# TSAL.net
KiCad netlist of a schematic drawn in EAGLE
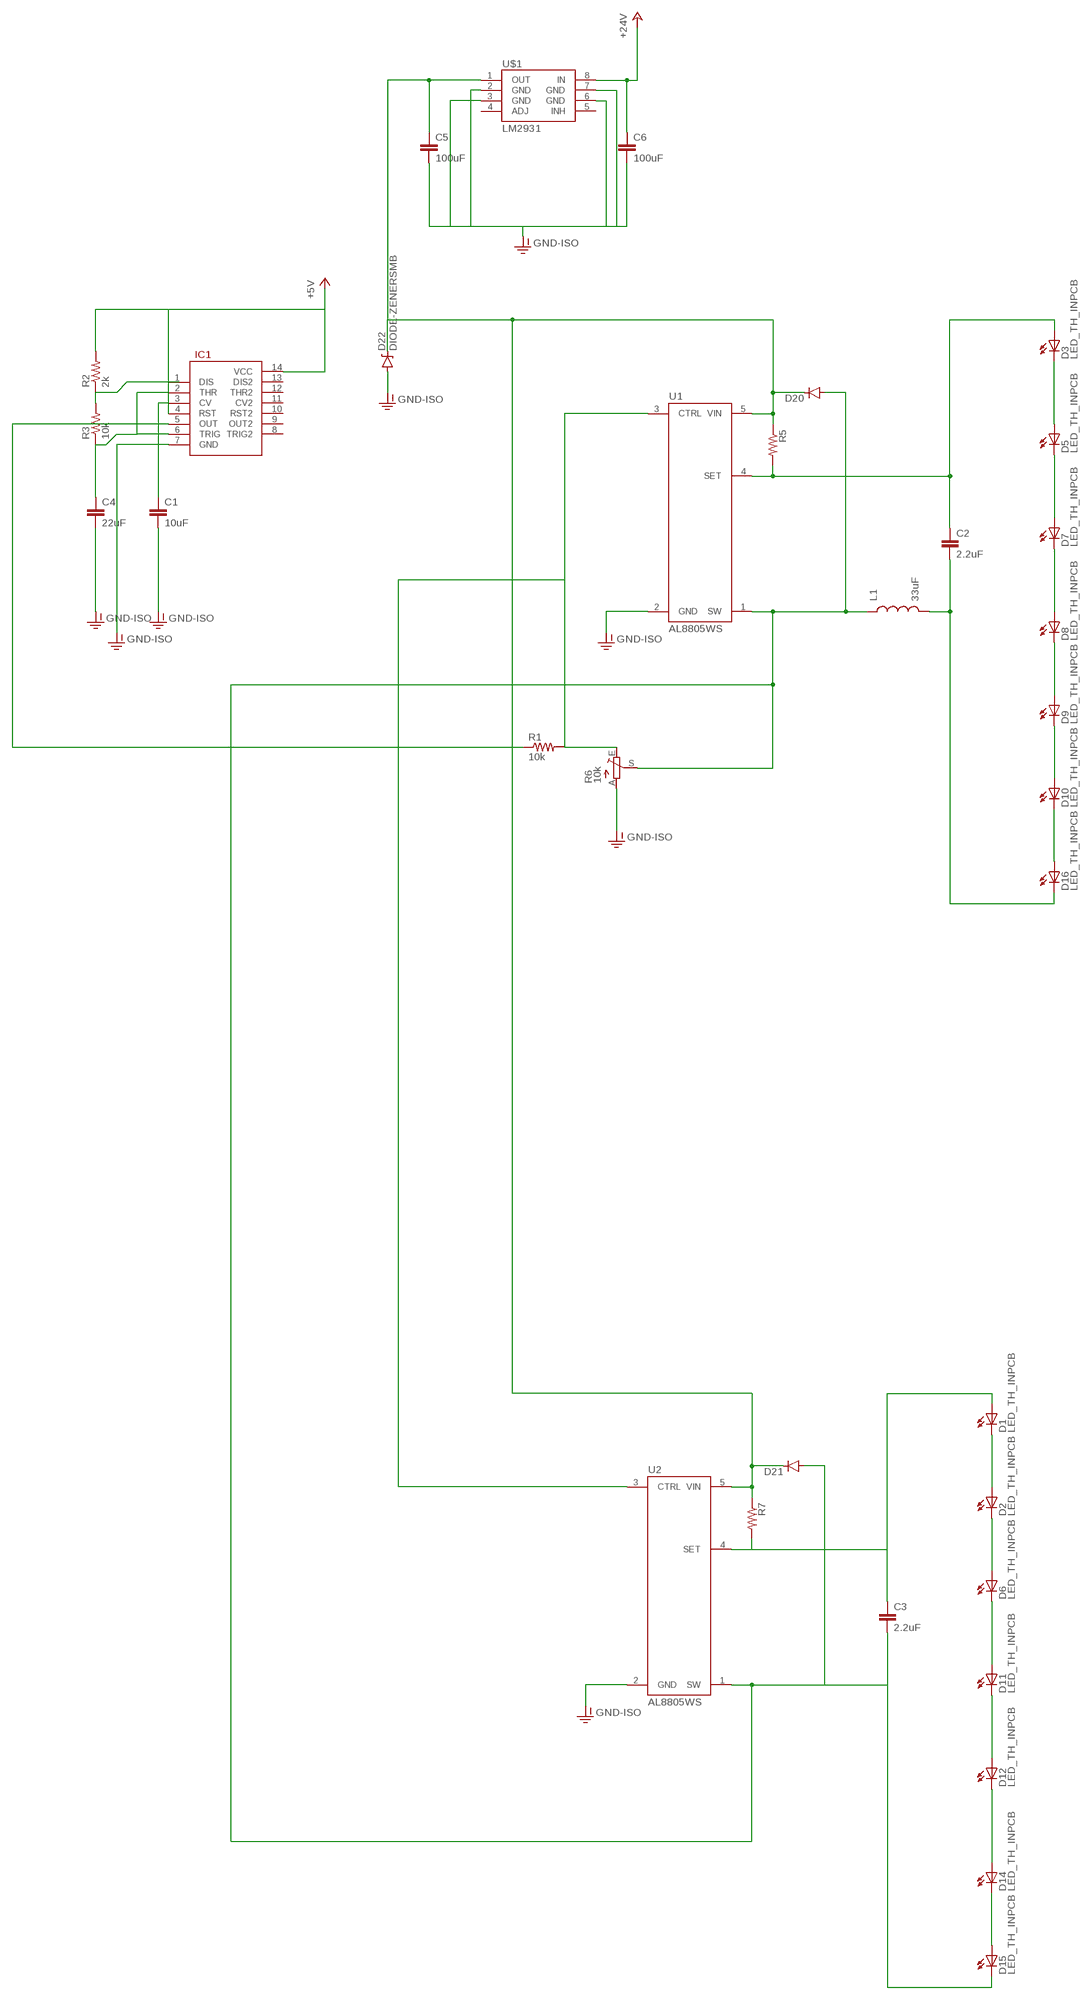
[diagram p0: schematic, sheet 1]

(export (version "E")
  (design (tool "Eeschema 10.0.6"))
  (components
    (comp (ref "C1")
      (value "10uF")
      (footprint "eagle-import:0805")
      (libsource (lib "eagle-import") (part "CAP0805"))
    )
    (comp (ref "C2")
      (value "2.2uF")
      (footprint "eagle-import:0805")
      (libsource (lib "eagle-import") (part "CAP0805"))
    )
    (comp (ref "C3")
      (value "2.2uF")
      (footprint "eagle-import:0805")
      (libsource (lib "eagle-import") (part "CAP0805"))
    )
    (comp (ref "C4")
      (value "22uF")
      (footprint "eagle-import:0805")
      (libsource (lib "eagle-import") (part "CAP0805"))
    )
    (comp (ref "C5")
      (value "100uF")
      (footprint "eagle-import:0805")
      (libsource (lib "eagle-import") (part "CAP0805"))
    )
    (comp (ref "C6")
      (value "100uF")
      (footprint "eagle-import:0805")
      (libsource (lib "eagle-import") (part "CAP0805"))
    )
    (comp (ref "D1")
      (value "LED_TH_INPCB")
      (footprint "eagle-import:5MM_TH_INDENT")
      (libsource (lib "eagle-import") (part "LED_TH_INPCB"))
    )
    (comp (ref "D2")
      (value "LED_TH_INPCB")
      (footprint "eagle-import:5MM_TH_INDENT")
      (libsource (lib "eagle-import") (part "LED_TH_INPCB"))
    )
    (comp (ref "D3")
      (value "LED_TH_INPCB")
      (footprint "eagle-import:5MM_TH_INDENT")
      (libsource (lib "eagle-import") (part "LED_TH_INPCB"))
    )
    (comp (ref "D5")
      (value "LED_TH_INPCB")
      (footprint "eagle-import:5MM_TH_INDENT")
      (libsource (lib "eagle-import") (part "LED_TH_INPCB"))
    )
    (comp (ref "D6")
      (value "LED_TH_INPCB")
      (footprint "eagle-import:5MM_TH_INDENT")
      (libsource (lib "eagle-import") (part "LED_TH_INPCB"))
    )
    (comp (ref "D7")
      (value "LED_TH_INPCB")
      (footprint "eagle-import:5MM_TH_INDENT")
      (libsource (lib "eagle-import") (part "LED_TH_INPCB"))
    )
    (comp (ref "D8")
      (value "LED_TH_INPCB")
      (footprint "eagle-import:5MM_TH_INDENT")
      (libsource (lib "eagle-import") (part "LED_TH_INPCB"))
    )
    (comp (ref "D9")
      (value "LED_TH_INPCB")
      (footprint "eagle-import:5MM_TH_INDENT")
      (libsource (lib "eagle-import") (part "LED_TH_INPCB"))
    )
    (comp (ref "D10")
      (value "LED_TH_INPCB")
      (footprint "eagle-import:5MM_TH_INDENT")
      (libsource (lib "eagle-import") (part "LED_TH_INPCB"))
    )
    (comp (ref "D11")
      (value "LED_TH_INPCB")
      (footprint "eagle-import:5MM_TH_INDENT")
      (libsource (lib "eagle-import") (part "LED_TH_INPCB"))
    )
    (comp (ref "D12")
      (value "LED_TH_INPCB")
      (footprint "eagle-import:5MM_TH_INDENT")
      (libsource (lib "eagle-import") (part "LED_TH_INPCB"))
    )
    (comp (ref "D14")
      (value "LED_TH_INPCB")
      (footprint "eagle-import:5MM_TH_INDENT")
      (libsource (lib "eagle-import") (part "LED_TH_INPCB"))
    )
    (comp (ref "D15")
      (value "LED_TH_INPCB")
      (footprint "eagle-import:5MM_TH_INDENT")
      (libsource (lib "eagle-import") (part "LED_TH_INPCB"))
    )
    (comp (ref "D16")
      (value "LED_TH_INPCB")
      (footprint "eagle-import:5MM_TH_INDENT")
      (libsource (lib "eagle-import") (part "LED_TH_INPCB"))
    )
    (comp (ref "D20")
      (value "DIODESMB")
      (footprint "eagle-import:SMB-DIODE")
      (libsource (lib "eagle-import") (part "DIODESMB"))
    )
    (comp (ref "D21")
      (value "DIODESMB")
      (footprint "eagle-import:SMB-DIODE")
      (libsource (lib "eagle-import") (part "DIODESMB"))
    )
    (comp (ref "D22")
      (value "DIODE-ZENERSMB")
      (footprint "eagle-import:SMB-DIODE")
      (libsource (lib "eagle-import") (part "DIODE-ZENERSMB"))
    )
    (comp (ref "IC1")
      (value "556")
      (footprint "eagle-import:DIL14")
      (libsource (lib "eagle-import") (part "556"))
    )
    (comp (ref "L1")
      (value "33uF")
      (footprint "eagle-import:0805")
      (libsource (lib "eagle-import") (part "INDUCTOR0805"))
    )
    (comp (ref "R1")
      (value "10k")
      (footprint "eagle-import:0805")
      (libsource (lib "eagle-import") (part "RESISTOR0805-RES"))
    )
    (comp (ref "R2")
      (value "2k")
      (footprint "eagle-import:0805")
      (libsource (lib "eagle-import") (part "RESISTOR0805-RES"))
    )
    (comp (ref "R3")
      (value "10k")
      (footprint "eagle-import:0805")
      (libsource (lib "eagle-import") (part "RESISTOR0805-RES"))
    )
    (comp (ref "R5")
      (value "RESISTOR0805-RES")
      (footprint "eagle-import:0805")
      (libsource (lib "eagle-import") (part "RESISTOR0805-RES"))
    )
    (comp (ref "R6")
      (value "10k")
      (footprint "eagle-import:B25P")
      (libsource (lib "eagle-import") (part "TRIM_EU-B25P"))
    )
    (comp (ref "R7")
      (value "RESISTOR0805-RES")
      (footprint "eagle-import:0805")
      (libsource (lib "eagle-import") (part "RESISTOR0805-RES"))
    )
    (comp (ref "U$1")
      (value "LM2931")
      (footprint "eagle-import:SO08")
      (libsource (lib "eagle-import") (part "LM2931"))
    )
    (comp (ref "U1")
      (value "AL8805WS")
      (footprint "eagle-import:SOT23-5")
      (libsource (lib "eagle-import") (part "AL8805"))
    )
    (comp (ref "U2")
      (value "AL8805WS")
      (footprint "eagle-import:SOT23-5")
      (libsource (lib "eagle-import") (part "AL8805"))
    )
  )
  (nets
    (net (code "1") (name "+5V") (class "Default")
      (node (ref "IC1") (pin "14") (pinfunction "VCC_14") (pintype "bidirectional"))
      (node (ref "IC1") (pin "4") (pinfunction "RST_4") (pintype "bidirectional"))
      (node (ref "R2") (pin "2") (pinfunction "2_2") (pintype "passive"))
    )
    (net (code "2") (name "+24V") (class "Default")
      (node (ref "C6") (pin "1") (pinfunction "1_1") (pintype "passive"))
      (node (ref "U$1") (pin "8") (pinfunction "IN_8") (pintype "bidirectional"))
    )
    (net (code "3") (name "GND-ISO") (class "Default")
      (node (ref "C1") (pin "2") (pinfunction "2_2") (pintype "passive"))
      (node (ref "C4") (pin "2") (pinfunction "2_2") (pintype "passive"))
      (node (ref "C5") (pin "2") (pinfunction "2_2") (pintype "passive"))
      (node (ref "C6") (pin "2") (pinfunction "2_2") (pintype "passive"))
      (node (ref "D22") (pin "A") (pinfunction "A_A") (pintype "passive"))
      (node (ref "IC1") (pin "7") (pinfunction "GND_7") (pintype "bidirectional"))
      (node (ref "R6") (pin "A") (pinfunction "A_A") (pintype "passive"))
      (node (ref "U$1") (pin "2") (pinfunction "GND_2") (pintype "bidirectional"))
      (node (ref "U$1") (pin "3") (pinfunction "GND_3") (pintype "bidirectional"))
      (node (ref "U$1") (pin "6") (pinfunction "GND_6") (pintype "bidirectional"))
      (node (ref "U$1") (pin "7") (pinfunction "GND_7") (pintype "bidirectional"))
      (node (ref "U1") (pin "2") (pinfunction "GND_2") (pintype "bidirectional"))
      (node (ref "U2") (pin "2") (pinfunction "GND_2") (pintype "bidirectional"))
    )
    (net (code "4") (name "Net-(C2-Pad2)") (class "Default")
      (node (ref "C2") (pin "2") (pinfunction "2_2") (pintype "passive"))
      (node (ref "D16") (pin "C") (pinfunction "C_C") (pintype "passive"))
      (node (ref "L1") (pin "2") (pinfunction "2_2") (pintype "passive"))
    )
    (net (code "5") (name "Net-(D1-PadC)") (class "Default")
      (node (ref "D1") (pin "C") (pinfunction "C_C") (pintype "passive"))
      (node (ref "D2") (pin "A") (pinfunction "A_A") (pintype "passive"))
    )
    (net (code "6") (name "Net-(D2-PadC)") (class "Default")
      (node (ref "D2") (pin "C") (pinfunction "C_C") (pintype "passive"))
      (node (ref "D6") (pin "A") (pinfunction "A_A") (pintype "passive"))
    )
    (net (code "7") (name "Net-(D3-PadC)") (class "Default")
      (node (ref "D3") (pin "C") (pinfunction "C_C") (pintype "passive"))
      (node (ref "D5") (pin "A") (pinfunction "A_A") (pintype "passive"))
    )
    (net (code "8") (name "Net-(D5-PadC)") (class "Default")
      (node (ref "D5") (pin "C") (pinfunction "C_C") (pintype "passive"))
      (node (ref "D7") (pin "A") (pinfunction "A_A") (pintype "passive"))
    )
    (net (code "9") (name "Net-(D7-PadC)") (class "Default")
      (node (ref "D7") (pin "C") (pinfunction "C_C") (pintype "passive"))
      (node (ref "D8") (pin "A") (pinfunction "A_A") (pintype "passive"))
    )
    (net (code "10") (name "Net-(D8-PadC)") (class "Default")
      (node (ref "D8") (pin "C") (pinfunction "C_C") (pintype "passive"))
      (node (ref "D9") (pin "A") (pinfunction "A_A") (pintype "passive"))
    )
    (net (code "11") (name "Net-(D10-PadA)") (class "Default")
      (node (ref "D10") (pin "A") (pinfunction "A_A") (pintype "passive"))
      (node (ref "D9") (pin "C") (pinfunction "C_C") (pintype "passive"))
    )
    (net (code "12") (name "Net-(D10-PadC)") (class "Default")
      (node (ref "D10") (pin "C") (pinfunction "C_C") (pintype "passive"))
      (node (ref "D16") (pin "A") (pinfunction "A_A") (pintype "passive"))
    )
    (net (code "13") (name "Net-(D11-PadA)") (class "Default")
      (node (ref "D11") (pin "A") (pinfunction "A_A") (pintype "passive"))
      (node (ref "D6") (pin "C") (pinfunction "C_C") (pintype "passive"))
    )
    (net (code "14") (name "Net-(D11-PadC)") (class "Default")
      (node (ref "D11") (pin "C") (pinfunction "C_C") (pintype "passive"))
      (node (ref "D12") (pin "A") (pinfunction "A_A") (pintype "passive"))
    )
    (net (code "15") (name "Net-(D12-PadC)") (class "Default")
      (node (ref "D12") (pin "C") (pinfunction "C_C") (pintype "passive"))
      (node (ref "D14") (pin "A") (pinfunction "A_A") (pintype "passive"))
    )
    (net (code "16") (name "Net-(D14-PadC)") (class "Default")
      (node (ref "D14") (pin "C") (pinfunction "C_C") (pintype "passive"))
      (node (ref "D15") (pin "A") (pinfunction "A_A") (pintype "passive"))
    )
    (net (code "17") (name "Net-(IC1-CV)") (class "Default")
      (node (ref "C1") (pin "1") (pinfunction "1_1") (pintype "passive"))
      (node (ref "IC1") (pin "3") (pinfunction "CV_3") (pintype "bidirectional"))
    )
    (net (code "18") (name "Net-(IC1-OUT)") (class "Default")
      (node (ref "IC1") (pin "5") (pinfunction "OUT_5") (pintype "bidirectional"))
      (node (ref "R1") (pin "1") (pinfunction "1_1") (pintype "passive"))
    )
    (net (code "19") (name "Net-(IC1-THR)") (class "Default")
      (node (ref "C4") (pin "1") (pinfunction "1_1") (pintype "passive"))
      (node (ref "IC1") (pin "2") (pinfunction "THR_2") (pintype "bidirectional"))
      (node (ref "IC1") (pin "6") (pinfunction "TRIG_6") (pintype "bidirectional"))
      (node (ref "R3") (pin "1") (pinfunction "1_1") (pintype "passive"))
    )
    (net (code "20") (name "Net-(R2-Pad1)") (class "Default")
      (node (ref "R2") (pin "1") (pinfunction "1_1") (pintype "passive"))
      (node (ref "R3") (pin "2") (pinfunction "2_2") (pintype "passive"))
    )
    (net (code "21") (name "Net-(U$1-OUT)") (class "Default")
      (node (ref "C5") (pin "1") (pinfunction "1_1") (pintype "passive"))
      (node (ref "D20") (pin "C") (pinfunction "C_C") (pintype "passive"))
      (node (ref "D21") (pin "C") (pinfunction "C_C") (pintype "passive"))
      (node (ref "D22") (pin "C") (pinfunction "C_C") (pintype "passive"))
      (node (ref "R5") (pin "1") (pinfunction "1_1") (pintype "passive"))
      (node (ref "R7") (pin "1") (pinfunction "1_1") (pintype "passive"))
      (node (ref "U$1") (pin "1") (pinfunction "OUT_1") (pintype "bidirectional"))
      (node (ref "U1") (pin "5") (pinfunction "VIN_5") (pintype "bidirectional"))
      (node (ref "U2") (pin "5") (pinfunction "VIN_5") (pintype "bidirectional"))
    )
    (net (code "22") (name "Net-(U1-CTRL)") (class "Default")
      (node (ref "R1") (pin "2") (pinfunction "2_2") (pintype "passive"))
      (node (ref "R6") (pin "E") (pinfunction "E_E") (pintype "passive"))
      (node (ref "U1") (pin "3") (pinfunction "CTRL_3") (pintype "bidirectional"))
      (node (ref "U2") (pin "3") (pinfunction "CTRL_3") (pintype "bidirectional"))
    )
    (net (code "23") (name "Net-(U1-SET)") (class "Default")
      (node (ref "C2") (pin "1") (pinfunction "1_1") (pintype "passive"))
      (node (ref "D3") (pin "A") (pinfunction "A_A") (pintype "passive"))
      (node (ref "R5") (pin "2") (pinfunction "2_2") (pintype "passive"))
      (node (ref "U1") (pin "4") (pinfunction "SET_4") (pintype "bidirectional"))
    )
    (net (code "24") (name "Net-(U1-SW)") (class "Default")
      (node (ref "C3") (pin "2") (pinfunction "2_2") (pintype "passive"))
      (node (ref "D15") (pin "C") (pinfunction "C_C") (pintype "passive"))
      (node (ref "D20") (pin "A") (pinfunction "A_A") (pintype "passive"))
      (node (ref "D21") (pin "A") (pinfunction "A_A") (pintype "passive"))
      (node (ref "L1") (pin "1") (pinfunction "1_1") (pintype "passive"))
      (node (ref "R6") (pin "S") (pinfunction "S_S") (pintype "passive"))
      (node (ref "U1") (pin "1") (pinfunction "SW_1") (pintype "bidirectional"))
      (node (ref "U2") (pin "1") (pinfunction "SW_1") (pintype "bidirectional"))
    )
    (net (code "25") (name "Net-(U2-SET)") (class "Default")
      (node (ref "C3") (pin "1") (pinfunction "1_1") (pintype "passive"))
      (node (ref "D1") (pin "A") (pinfunction "A_A") (pintype "passive"))
      (node (ref "R7") (pin "2") (pinfunction "2_2") (pintype "passive"))
      (node (ref "U2") (pin "4") (pinfunction "SET_4") (pintype "bidirectional"))
    )
    (net (code "26") (name "unconnected-(IC1-CV2-Pad11)") (class "Default")
      (node (ref "IC1") (pin "11") (pinfunction "CV2_11") (pintype "bidirectional"))
    )
    (net (code "27") (name "unconnected-(IC1-DIS-Pad1)") (class "Default")
      (node (ref "IC1") (pin "1") (pinfunction "DIS_1") (pintype "bidirectional"))
    )
    (net (code "28") (name "unconnected-(IC1-DIS2-Pad13)") (class "Default")
      (node (ref "IC1") (pin "13") (pinfunction "DIS2_13") (pintype "bidirectional"))
    )
    (net (code "29") (name "unconnected-(IC1-OUT2-Pad9)") (class "Default")
      (node (ref "IC1") (pin "9") (pinfunction "OUT2_9") (pintype "bidirectional"))
    )
    (net (code "30") (name "unconnected-(IC1-RST2-Pad10)") (class "Default")
      (node (ref "IC1") (pin "10") (pinfunction "RST2_10") (pintype "bidirectional"))
    )
    (net (code "31") (name "unconnected-(IC1-THR2-Pad12)") (class "Default")
      (node (ref "IC1") (pin "12") (pinfunction "THR2_12") (pintype "bidirectional"))
    )
    (net (code "32") (name "unconnected-(IC1-TRIG2-Pad8)") (class "Default")
      (node (ref "IC1") (pin "8") (pinfunction "TRIG2_8") (pintype "bidirectional"))
    )
    (net (code "33") (name "unconnected-(U$1-ADJ-Pad4)") (class "Default")
      (node (ref "U$1") (pin "4") (pinfunction "ADJ_4") (pintype "bidirectional"))
    )
    (net (code "34") (name "unconnected-(U$1-INH-Pad5)") (class "Default")
      (node (ref "U$1") (pin "5") (pinfunction "INH_5") (pintype "bidirectional"))
    )
  )
)
